# Sensor_Controller.net
KiCad netlist of a schematic drawn in Altium Designer
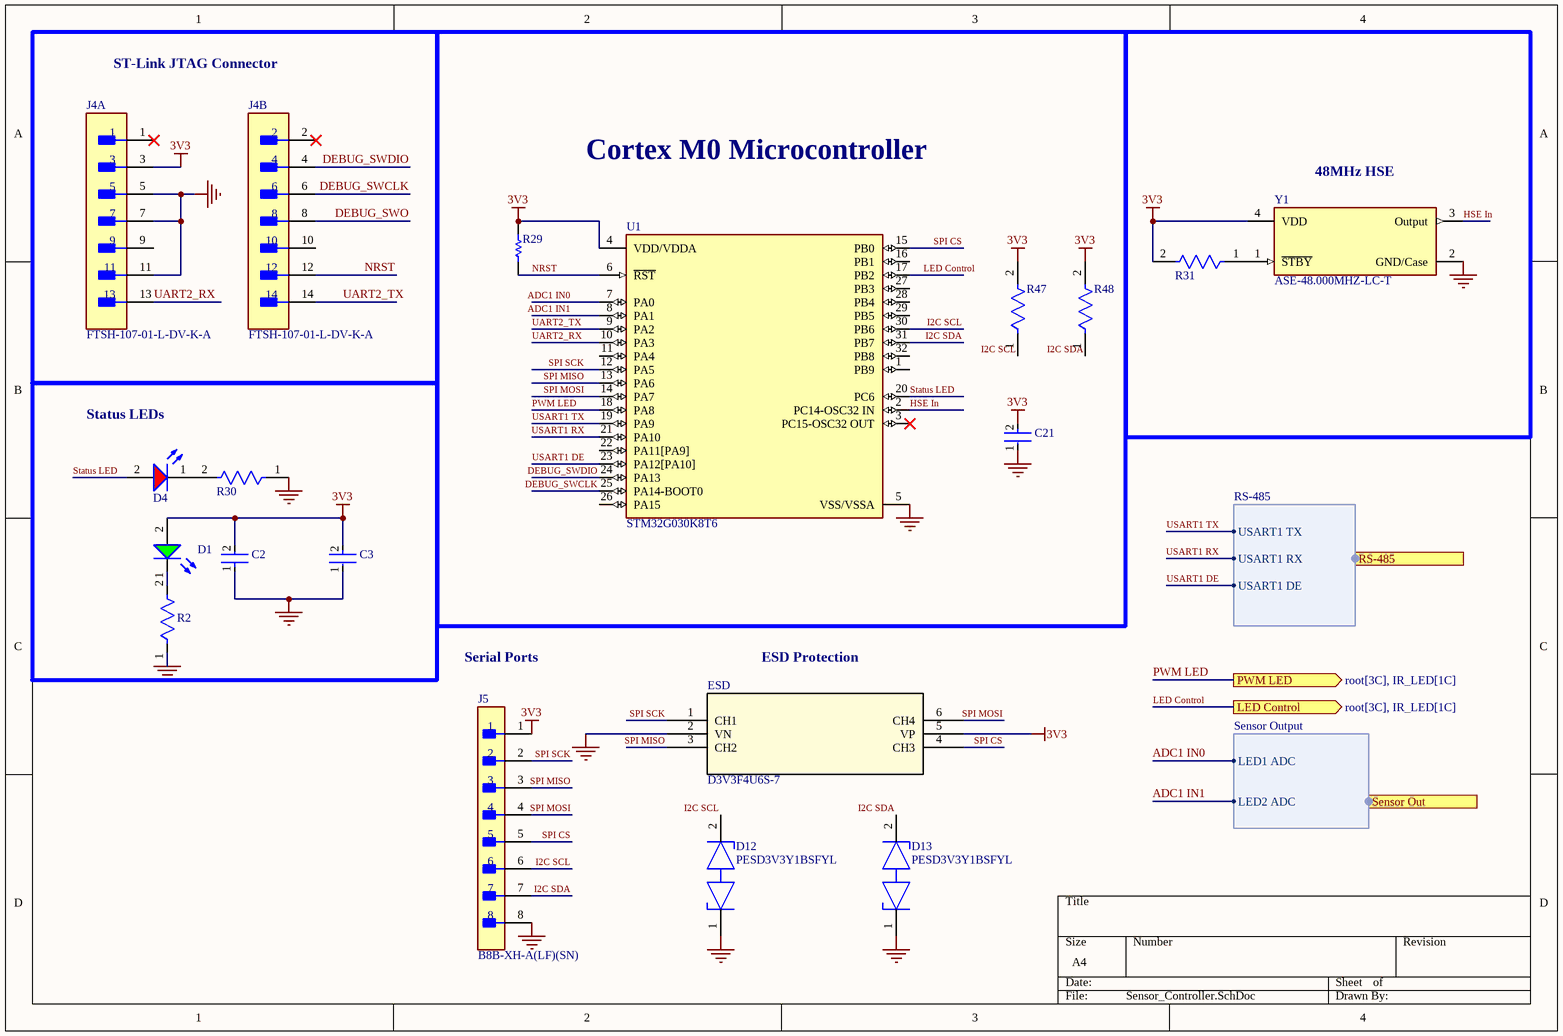
[diagram p0: Sensor_Controller.SchDoc]

(export (version "E")
  (design (tool "Eeschema 10.0.6"))
  (components
    (comp (ref "C2")
      (value "GRM188R6YA475KE15D")
      (footprint "FP-GRM188-0_2-IPC_C")
      (description "Chip Multilayer Ceramic Capacitors for General Purpose, 0603, 4.7uF, X5R, 15%, 10%, 35V")
      (fields (field (name "VOLTAGE") "35V") (field (name "TOLERANCE") "10%"))
      (libsource (lib "Altium Content Vault") (part "11868f565c42a9108669ba33697ecf6"))
    )
    (comp (ref "C3")
      (value "GRM155R71C104KA88D")
      (footprint "FP-GRM15-MFG")
      (description "CAP CER 0.1UF 16V X7R 0402")
      (fields
        (field (name "TOLERANCE") "10%")
        (field (name "OCTOPART") "https://octopart.com/grm155r71c104ka88d-murata-196880")
      )
      (libsource (lib "Altium Content Vault") (part "236180d848d6139a670b325ea6854c9"))
    )
    (comp (ref "C21")
      (value "GRM155R71C104KA88D")
      (footprint "FP-GRM15-MFG")
      (description "CAP CER 0.1UF 16V X7R 0402")
      (fields
        (field (name "TOLERANCE") "10%")
        (field (name "OCTOPART") "https://octopart.com/grm155r71c104ka88d-murata-196880")
      )
      (libsource (lib "Altium Content Vault") (part "236180d848d6139a670b325ea6854c9"))
    )
    (comp (ref "D1")
      (value "150060VS75000")
      (footprint "WL-SMCW_0603_150060xx75000")
      (description "WURTH ELEKTRONIK - 150060VS75000 - LED, Green, SMD, 0603, 30 mA, 2 V, 570 nm")
      (libsource (lib "Altium Content Vault") (part "LED_Green_2A-1K"))
    )
    (comp (ref "D4")
      (value "150060SS75000")
      (footprint "WL-SMCW_0603_150060xx75000")
      (description "Led, Red, 630 Nm, 1.9 V, 30 Ma, 60 Mcd Rohs Compliant: Yes")
      (libsource (lib "Altium Content Vault") (part "LED_Red_2A-1K"))
    )
    (comp (ref "D12")
      (value "PESD3V3Y1BSFYL")
      (footprint "FP-SOD962-2-CA-MFG")
      (description "PESD3V3Y1BSFYL PESD4V0Y1BSF - Extremely low capacitance bidirectional ESD protection diode")
      (libsource (lib "Altium Content Vault") (part "3f15ade4c48aeaca3578241bea7d4a4"))
    )
    (comp (ref "D13")
      (value "PESD3V3Y1BSFYL")
      (footprint "FP-SOD962-2-CA-MFG")
      (description "PESD3V3Y1BSFYL PESD4V0Y1BSF - Extremely low capacitance bidirectional ESD protection diode")
      (libsource (lib "Altium Content Vault") (part "3f15ade4c48aeaca3578241bea7d4a4"))
    )
    (comp (ref "ESD")
      (value "D3V3F4U6S-7")
      (footprint "SOT-363_DIO")
      (description "No Description Available")
      (fields (field (name "COPYRIGHT") "Copyright (C) 2026 Ultra Librarian. All rights reserved."))
      (libsource (lib "D3V3F4U6S-7") (part "D3V3F4U6S-7"))
    )
    (comp (ref "J4")
      (value "FTSH-107-01-L-DV-K-A")
      (footprint "FP-FTSH-107-01-L-DV-K-A-MFG")
      (description "CONN HEADER SMD 14POS 1.27MM")
      (libsource (lib "Altium Content Vault") (part "45cc164b9edde9e1ad516d884ad4e1e"))
    )
    (comp (ref "J5")
      (value "B8B-XH-A(LF)(SN)")
      (footprint "FP-B8B-XH-A_LF_SN-MFG")
      (description "CONN HEADER VERT 8POS 2.5MM")
      (libsource (lib "Altium Content Vault") (part "99ec2b232beb5d2356d4d77f6a047f0"))
    )
    (comp (ref "R2")
      (value "RC0603FR-0710KL")
      (footprint "FP-RC0603-0_55-IPC_C")
      (description "RES 10K OHM 1% 1/10W 0603")
      (fields (field (name "TOLERANCE") "1%"))
      (libsource (lib "Altium Content Vault") (part "1029c3af85768c4190bb7ad29bc67b5"))
    )
    (comp (ref "R29")
      (value "TNPW040210K0DEED")
      (footprint "RESC1005X40X20NL05T10")
      (fields (field (name "MANUFACTURER") "Vishay BCcomponents"))
      (libsource (lib "Altium Content Vault") (part "RES"))
    )
    (comp (ref "R30")
      (value "RC0603FR-0710KL")
      (footprint "FP-RC0603-0_55-IPC_C")
      (description "RES 10K OHM 1% 1/10W 0603")
      (fields (field (name "TOLERANCE") "1%"))
      (libsource (lib "Altium Content Vault") (part "1029c3af85768c4190bb7ad29bc67b5"))
    )
    (comp (ref "R31")
      (value "RC0603FR-0710KL")
      (footprint "FP-RC0603-0_55-IPC_C")
      (description "RES 10K OHM 1% 1/10W 0603")
      (fields (field (name "TOLERANCE") "1%"))
      (libsource (lib "Altium Content Vault") (part "1029c3af85768c4190bb7ad29bc67b5"))
    )
    (comp (ref "R47")
      (value "CRCW08053K30JNEC")
      (footprint "FP-CRCW0805-e3-IPC_A")
      (description "RES Thick Film, 3.3kΩ, 5%, 0.125W, 200ppm/°C, 0805")
      (fields (field (name "TOLERANCE") "5%"))
      (libsource (lib "Altium Content Vault") (part "1029c3af85768c4190bb7ad29bc67b5"))
    )
    (comp (ref "R48")
      (value "CRCW08053K30JNEC")
      (footprint "FP-CRCW0805-e3-IPC_A")
      (description "RES Thick Film, 3.3kΩ, 5%, 0.125W, 200ppm/°C, 0805")
      (fields (field (name "TOLERANCE") "5%"))
      (libsource (lib "Altium Content Vault") (part "1029c3af85768c4190bb7ad29bc67b5"))
    )
    (comp (ref "U1")
      (value "STM32G030K8T6")
      (footprint "FP-LQFP32-5V-IPC_A")
      (description "IC MCU 32BIT 64KB FLASH 32LQFP")
      (libsource (lib "Altium Content Vault") (part "fea91388a178aa646681c81fcef9c35"))
    )
    (comp (ref "Y1")
      (value "ASE-48.000MHZ-LC-T")
      (footprint "FP-ASE-MFG")
      (description "XTAL Oscillator 48MHz ±50ppm CMOS 3.3V 4-SMD 3.2mm x 2.5mm")
      (libsource (lib "Altium Content Vault") (part "61a724e6190563596ac712fef61ad37"))
    )
  )
  (nets
    (net (code "4") (name "/ADC1 IN0") (class "Default")
      (node (ref "U1") (pin "7") (pinfunction "PA0_7") (pintype "bidirectional"))
    )
    (net (code "5") (name "/ADC1 IN1") (class "Default")
      (node (ref "U1") (pin "8") (pinfunction "PA1_8") (pintype "bidirectional"))
    )
    (net (code "6") (name "/DEBUG_SWCLK") (class "Default")
      (node (ref "J4") (pin "6") (pinfunction "6_6") (pintype "passive"))
      (node (ref "U1") (pin "25") (pinfunction "PA14-BOOT0_25") (pintype "bidirectional"))
    )
    (net (code "7") (name "/DEBUG_SWDIO") (class "Default")
      (node (ref "J4") (pin "4") (pinfunction "4_4") (pintype "passive"))
      (node (ref "U1") (pin "24") (pinfunction "PA13_24") (pintype "bidirectional"))
    )
    (net (code "8") (name "/DEBUG_SWO") (class "Default")
      (node (ref "J4") (pin "8") (pinfunction "8_8") (pintype "passive"))
    )
    (net (code "9") (name "/HSE In") (class "Default")
      (node (ref "U1") (pin "2") (pinfunction "PC14-OSC32_IN_2") (pintype "bidirectional"))
      (node (ref "Y1") (pin "3") (pinfunction "Output_3") (pintype "output"))
    )
    (net (code "10") (name "/I2C SCL") (class "Default")
      (node (ref "D12") (pin "2") (pinfunction "2_2") (pintype "passive"))
      (node (ref "J5") (pin "6") (pinfunction "6_6") (pintype "passive"))
      (node (ref "R47") (pin "1") (pinfunction "1_1") (pintype "passive"))
      (node (ref "U1") (pin "30") (pinfunction "PB6_30") (pintype "bidirectional"))
    )
    (net (code "11") (name "/I2C SDA") (class "Default")
      (node (ref "D13") (pin "2") (pinfunction "2_2") (pintype "passive"))
      (node (ref "J5") (pin "7") (pinfunction "7_7") (pintype "passive"))
      (node (ref "R48") (pin "1") (pinfunction "1_1") (pintype "passive"))
      (node (ref "U1") (pin "31") (pinfunction "PB7_31") (pintype "bidirectional"))
    )
    (net (code "12") (name "/LED Control") (class "Default")
      (node (ref "U1") (pin "17") (pinfunction "PB2_17") (pintype "bidirectional"))
    )
    (net (code "13") (name "/NRST") (class "Default")
      (node (ref "J4") (pin "12") (pinfunction "12_12") (pintype "passive"))
      (node (ref "R29") (pin "1") (pinfunction "1_1") (pintype "passive"))
      (node (ref "U1") (pin "6") (pinfunction "~{RST}_6") (pintype "input"))
    )
    (net (code "14") (name "/PWM LED") (class "Default")
      (node (ref "U1") (pin "18") (pinfunction "PA8_18") (pintype "bidirectional"))
    )
    (net (code "15") (name "/SPI CS") (class "Default")
      (node (ref "ESD") (pin "4") (pinfunction "CH3_4") (pintype "passive"))
      (node (ref "J5") (pin "5") (pinfunction "5_5") (pintype "passive"))
      (node (ref "U1") (pin "15") (pinfunction "PB0_15") (pintype "bidirectional"))
    )
    (net (code "16") (name "/SPI MISO") (class "Default")
      (node (ref "ESD") (pin "3") (pinfunction "CH2_3") (pintype "passive"))
      (node (ref "J5") (pin "3") (pinfunction "3_3") (pintype "passive"))
      (node (ref "U1") (pin "13") (pinfunction "PA6_13") (pintype "bidirectional"))
    )
    (net (code "17") (name "/SPI MOSI") (class "Default")
      (node (ref "ESD") (pin "6") (pinfunction "CH4_6") (pintype "passive"))
      (node (ref "J5") (pin "4") (pinfunction "4_4") (pintype "passive"))
      (node (ref "U1") (pin "14") (pinfunction "PA7_14") (pintype "bidirectional"))
    )
    (net (code "18") (name "/SPI SCK") (class "Default")
      (node (ref "ESD") (pin "1") (pinfunction "CH1_1") (pintype "passive"))
      (node (ref "J5") (pin "2") (pinfunction "2_2") (pintype "passive"))
      (node (ref "U1") (pin "12") (pinfunction "PA5_12") (pintype "bidirectional"))
    )
    (net (code "19") (name "/Status LED") (class "Default")
      (node (ref "D4") (pin "2") (pinfunction "A_2") (pintype "passive"))
      (node (ref "U1") (pin "20") (pinfunction "PC6_20") (pintype "bidirectional"))
    )
    (net (code "20") (name "/UART2_RX") (class "Default")
      (node (ref "J4") (pin "13") (pinfunction "13_13") (pintype "passive"))
      (node (ref "U1") (pin "10") (pinfunction "PA3_10") (pintype "bidirectional"))
    )
    (net (code "21") (name "/UART2_TX") (class "Default")
      (node (ref "J4") (pin "14") (pinfunction "14_14") (pintype "passive"))
      (node (ref "U1") (pin "9") (pinfunction "PA2_9") (pintype "bidirectional"))
    )
    (net (code "22") (name "/USART1 DE") (class "Default")
      (node (ref "U1") (pin "23") (pinfunction "PA12[PA10]_23") (pintype "bidirectional"))
    )
    (net (code "23") (name "/USART1 RX") (class "Default")
      (node (ref "U1") (pin "21") (pinfunction "PA10_21") (pintype "bidirectional"))
    )
    (net (code "24") (name "/USART1 TX") (class "Default")
      (node (ref "U1") (pin "19") (pinfunction "PA9_19") (pintype "bidirectional"))
    )
    (net (code "27") (name "3V3") (class "Default")
      (node (ref "C2") (pin "2") (pinfunction "2_2") (pintype "passive"))
      (node (ref "C21") (pin "2") (pinfunction "2_2") (pintype "passive"))
      (node (ref "C3") (pin "2") (pinfunction "2_2") (pintype "passive"))
      (node (ref "D1") (pin "2") (pinfunction "A_2") (pintype "passive"))
      (node (ref "ESD") (pin "5") (pinfunction "VP_5") (pintype "power_in"))
      (node (ref "J4") (pin "3") (pinfunction "3_3") (pintype "passive"))
      (node (ref "J5") (pin "1") (pinfunction "1_1") (pintype "passive"))
      (node (ref "R29") (pin "2") (pinfunction "2_2") (pintype "passive"))
      (node (ref "R31") (pin "2") (pinfunction "2_2") (pintype "passive"))
      (node (ref "R47") (pin "2") (pinfunction "2_2") (pintype "passive"))
      (node (ref "R48") (pin "2") (pinfunction "2_2") (pintype "passive"))
      (node (ref "U1") (pin "4") (pinfunction "VDD/VDDA_4") (pintype "power_in"))
      (node (ref "Y1") (pin "4") (pinfunction "VDD_4") (pintype "power_in"))
    )
    (net (code "28") (name "GND") (class "Default")
      (node (ref "C2") (pin "1") (pinfunction "1_1") (pintype "passive"))
      (node (ref "C21") (pin "1") (pinfunction "1_1") (pintype "passive"))
      (node (ref "C3") (pin "1") (pinfunction "1_1") (pintype "passive"))
      (node (ref "D12") (pin "1") (pinfunction "1_1") (pintype "passive"))
      (node (ref "D13") (pin "1") (pinfunction "1_1") (pintype "passive"))
      (node (ref "ESD") (pin "2") (pinfunction "VN_2") (pintype "power_in"))
      (node (ref "J4") (pin "11") (pinfunction "11_11") (pintype "passive"))
      (node (ref "J4") (pin "5") (pinfunction "5_5") (pintype "passive"))
      (node (ref "J4") (pin "7") (pinfunction "7_7") (pintype "passive"))
      (node (ref "J5") (pin "8") (pinfunction "8_8") (pintype "passive"))
      (node (ref "R2") (pin "1") (pinfunction "1_1") (pintype "passive"))
      (node (ref "R30") (pin "1") (pinfunction "1_1") (pintype "passive"))
      (node (ref "U1") (pin "5") (pinfunction "VSS/VSSA_5") (pintype "power_in"))
      (node (ref "Y1") (pin "2") (pinfunction "GND/Case_2") (pintype "power_in"))
    )
    (net (code "29") (name "Net-(D1-K)") (class "Default")
      (node (ref "D1") (pin "1") (pinfunction "K_1") (pintype "passive"))
      (node (ref "R2") (pin "2") (pinfunction "2_2") (pintype "passive"))
    )
    (net (code "30") (name "Net-(D4-K)") (class "Default")
      (node (ref "D4") (pin "1") (pinfunction "K_1") (pintype "passive"))
      (node (ref "R30") (pin "2") (pinfunction "2_2") (pintype "passive"))
    )
    (net (code "31") (name "Net-(Y1-~{STBY})") (class "Default")
      (node (ref "R31") (pin "1") (pinfunction "1_1") (pintype "passive"))
      (node (ref "Y1") (pin "1") (pinfunction "~{STBY}_1") (pintype "input"))
    )
    (net (code "32") (name "unconnected-(J4-Pad1)") (class "Default")
      (node (ref "J4") (pin "1") (pinfunction "1_1") (pintype "passive+no_connect"))
    )
    (net (code "33") (name "unconnected-(J4-Pad2)") (class "Default")
      (node (ref "J4") (pin "2") (pinfunction "2_2") (pintype "passive+no_connect"))
    )
    (net (code "34") (name "unconnected-(J4-Pad9)") (class "Default")
      (node (ref "J4") (pin "9") (pinfunction "9_9") (pintype "passive"))
    )
    (net (code "35") (name "unconnected-(J4-Pad10)") (class "Default")
      (node (ref "J4") (pin "10") (pinfunction "10_10") (pintype "passive"))
    )
    (net (code "36") (name "unconnected-(U1-PA4-Pad11)") (class "Default")
      (node (ref "U1") (pin "11") (pinfunction "PA4_11") (pintype "bidirectional"))
    )
    (net (code "37") (name "unconnected-(U1-PA11[PA9]-Pad22)") (class "Default")
      (node (ref "U1") (pin "22") (pinfunction "PA11[PA9]_22") (pintype "bidirectional"))
    )
    (net (code "38") (name "unconnected-(U1-PA15-Pad26)") (class "Default")
      (node (ref "U1") (pin "26") (pinfunction "PA15_26") (pintype "bidirectional"))
    )
    (net (code "39") (name "unconnected-(U1-PB1-Pad16)") (class "Default")
      (node (ref "U1") (pin "16") (pinfunction "PB1_16") (pintype "bidirectional"))
    )
    (net (code "40") (name "unconnected-(U1-PB3-Pad27)") (class "Default")
      (node (ref "U1") (pin "27") (pinfunction "PB3_27") (pintype "bidirectional"))
    )
    (net (code "41") (name "unconnected-(U1-PB4-Pad28)") (class "Default")
      (node (ref "U1") (pin "28") (pinfunction "PB4_28") (pintype "bidirectional"))
    )
    (net (code "42") (name "unconnected-(U1-PB5-Pad29)") (class "Default")
      (node (ref "U1") (pin "29") (pinfunction "PB5_29") (pintype "bidirectional"))
    )
    (net (code "43") (name "unconnected-(U1-PB8-Pad32)") (class "Default")
      (node (ref "U1") (pin "32") (pinfunction "PB8_32") (pintype "bidirectional"))
    )
    (net (code "44") (name "unconnected-(U1-PB9-Pad1)") (class "Default")
      (node (ref "U1") (pin "1") (pinfunction "PB9_1") (pintype "bidirectional"))
    )
    (net (code "45") (name "unconnected-(U1-PC15-OSC32_OUT-Pad3)") (class "Default")
      (node (ref "U1") (pin "3") (pinfunction "PC15-OSC32_OUT_3") (pintype "bidirectional+no_connect"))
    )
  )
)
